# ohms-law-1.net
KiCad netlist of a schematic drawn in EAGLE
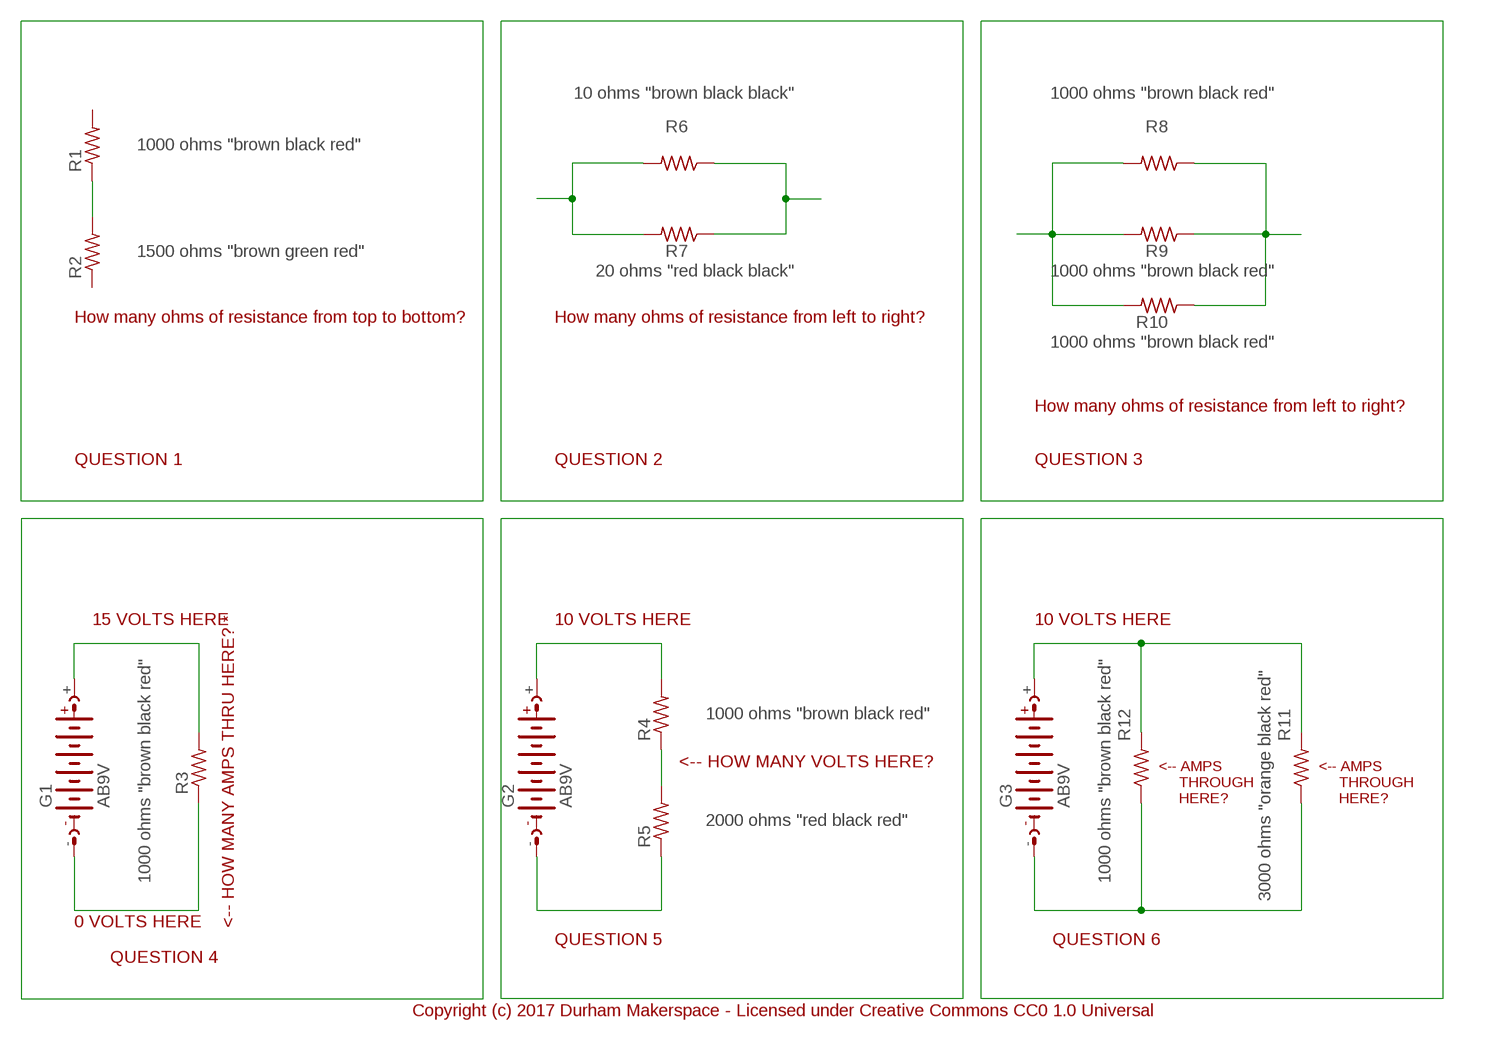
[diagram p0: schematic, sheet 1]

(export (version "E")
  (design (tool "Eeschema 10.0.6"))
  (components
    (comp (ref "G1")
      (value "AB9V")
      (footprint "eagle-import:AB9V")
      (libsource (lib "eagle-import") (part "AB9V"))
    )
    (comp (ref "G2")
      (value "AB9V")
      (footprint "eagle-import:AB9V")
      (libsource (lib "eagle-import") (part "AB9V"))
    )
    (comp (ref "G3")
      (value "AB9V")
      (footprint "eagle-import:AB9V")
      (libsource (lib "eagle-import") (part "AB9V"))
    )
    (comp (ref "R1")
      (value "1000 ohms \"brown black red\"")
      (footprint "eagle-import:M0805")
      (libsource (lib "eagle-import") (part "R-US_M0805"))
    )
    (comp (ref "R2")
      (value "1500 ohms \"brown green red\"")
      (footprint "eagle-import:M0805")
      (libsource (lib "eagle-import") (part "R-US_M0805"))
    )
    (comp (ref "R3")
      (value "1000 ohms \"brown black red\"")
      (footprint "eagle-import:M0805")
      (libsource (lib "eagle-import") (part "R-US_M0805"))
    )
    (comp (ref "R4")
      (value "1000 ohms \"brown black red\"")
      (footprint "eagle-import:M0805")
      (libsource (lib "eagle-import") (part "R-US_M0805"))
    )
    (comp (ref "R5")
      (value "2000 ohms \"red black red\"")
      (footprint "eagle-import:M0805")
      (libsource (lib "eagle-import") (part "R-US_M0805"))
    )
    (comp (ref "R6")
      (value "10 ohms \"brown black black\"")
      (footprint "eagle-import:M0805")
      (libsource (lib "eagle-import") (part "R-US_M0805"))
    )
    (comp (ref "R7")
      (value "20 ohms \"red black black\"")
      (footprint "eagle-import:M0805")
      (libsource (lib "eagle-import") (part "R-US_M0805"))
    )
    (comp (ref "R8")
      (value "1000 ohms \"brown black red\"")
      (footprint "eagle-import:M0805")
      (libsource (lib "eagle-import") (part "R-US_M0805"))
    )
    (comp (ref "R9")
      (value "1000 ohms \"brown black red\"")
      (footprint "eagle-import:M0805")
      (libsource (lib "eagle-import") (part "R-US_M0805"))
    )
    (comp (ref "R10")
      (value "1000 ohms \"brown black red\"")
      (footprint "eagle-import:M0805")
      (libsource (lib "eagle-import") (part "R-US_M0805"))
    )
    (comp (ref "R11")
      (value "3000 ohms \"orange black red\"")
      (footprint "eagle-import:M0805")
      (libsource (lib "eagle-import") (part "R-US_M0805"))
    )
    (comp (ref "R12")
      (value "1000 ohms \"brown black red\"")
      (footprint "eagle-import:M0805")
      (libsource (lib "eagle-import") (part "R-US_M0805"))
    )
  )
  (nets
    (net (code "4") (name "Net-(G1-Pad+)") (class "Default")
      (node (ref "G1") (pin "+") (pinfunction "+_+") (pintype "passive"))
      (node (ref "R3") (pin "2") (pinfunction "2_2") (pintype "passive"))
    )
    (net (code "5") (name "Net-(G1-Pad-)") (class "Default")
      (node (ref "G1") (pin "-") (pinfunction "-_-") (pintype "passive"))
      (node (ref "R3") (pin "1") (pinfunction "1_1") (pintype "passive"))
    )
    (net (code "6") (name "Net-(G2-Pad+)") (class "Default")
      (node (ref "G2") (pin "+") (pinfunction "+_+") (pintype "passive"))
      (node (ref "R4") (pin "2") (pinfunction "2_2") (pintype "passive"))
    )
    (net (code "7") (name "Net-(G2-Pad-)") (class "Default")
      (node (ref "G2") (pin "-") (pinfunction "-_-") (pintype "passive"))
      (node (ref "R5") (pin "1") (pinfunction "1_1") (pintype "passive"))
    )
    (net (code "8") (name "Net-(G3-Pad+)") (class "Default")
      (node (ref "G3") (pin "+") (pinfunction "+_+") (pintype "passive"))
      (node (ref "R11") (pin "2") (pinfunction "2_2") (pintype "passive"))
      (node (ref "R12") (pin "2") (pinfunction "2_2") (pintype "passive"))
    )
    (net (code "9") (name "Net-(G3-Pad-)") (class "Default")
      (node (ref "G3") (pin "-") (pinfunction "-_-") (pintype "passive"))
      (node (ref "R11") (pin "1") (pinfunction "1_1") (pintype "passive"))
      (node (ref "R12") (pin "1") (pinfunction "1_1") (pintype "passive"))
    )
    (net (code "10") (name "Net-(R1-Pad1)") (class "Default")
      (node (ref "R1") (pin "1") (pinfunction "1_1") (pintype "passive"))
      (node (ref "R2") (pin "2") (pinfunction "2_2") (pintype "passive"))
    )
    (net (code "11") (name "Net-(R4-Pad1)") (class "Default")
      (node (ref "R4") (pin "1") (pinfunction "1_1") (pintype "passive"))
      (node (ref "R5") (pin "2") (pinfunction "2_2") (pintype "passive"))
    )
    (net (code "12") (name "Net-(R6-Pad1)") (class "Default")
      (node (ref "R6") (pin "1") (pinfunction "1_1") (pintype "passive"))
      (node (ref "R7") (pin "1") (pinfunction "1_1") (pintype "passive"))
    )
    (net (code "13") (name "Net-(R6-Pad2)") (class "Default")
      (node (ref "R6") (pin "2") (pinfunction "2_2") (pintype "passive"))
      (node (ref "R7") (pin "2") (pinfunction "2_2") (pintype "passive"))
    )
    (net (code "14") (name "Net-(R10-Pad1)") (class "Default")
      (node (ref "R10") (pin "1") (pinfunction "1_1") (pintype "passive"))
      (node (ref "R8") (pin "1") (pinfunction "1_1") (pintype "passive"))
      (node (ref "R9") (pin "1") (pinfunction "1_1") (pintype "passive"))
    )
    (net (code "15") (name "Net-(R10-Pad2)") (class "Default")
      (node (ref "R10") (pin "2") (pinfunction "2_2") (pintype "passive"))
      (node (ref "R8") (pin "2") (pinfunction "2_2") (pintype "passive"))
      (node (ref "R9") (pin "2") (pinfunction "2_2") (pintype "passive"))
    )
    (net (code "16") (name "unconnected-(R1-Pad2)") (class "Default")
      (node (ref "R1") (pin "2") (pinfunction "2_2") (pintype "passive"))
    )
    (net (code "17") (name "unconnected-(R2-Pad1)") (class "Default")
      (node (ref "R2") (pin "1") (pinfunction "1_1") (pintype "passive"))
    )
  )
)
